# Solder_v2.net
KiCad netlist of a schematic drawn in EasyEDA
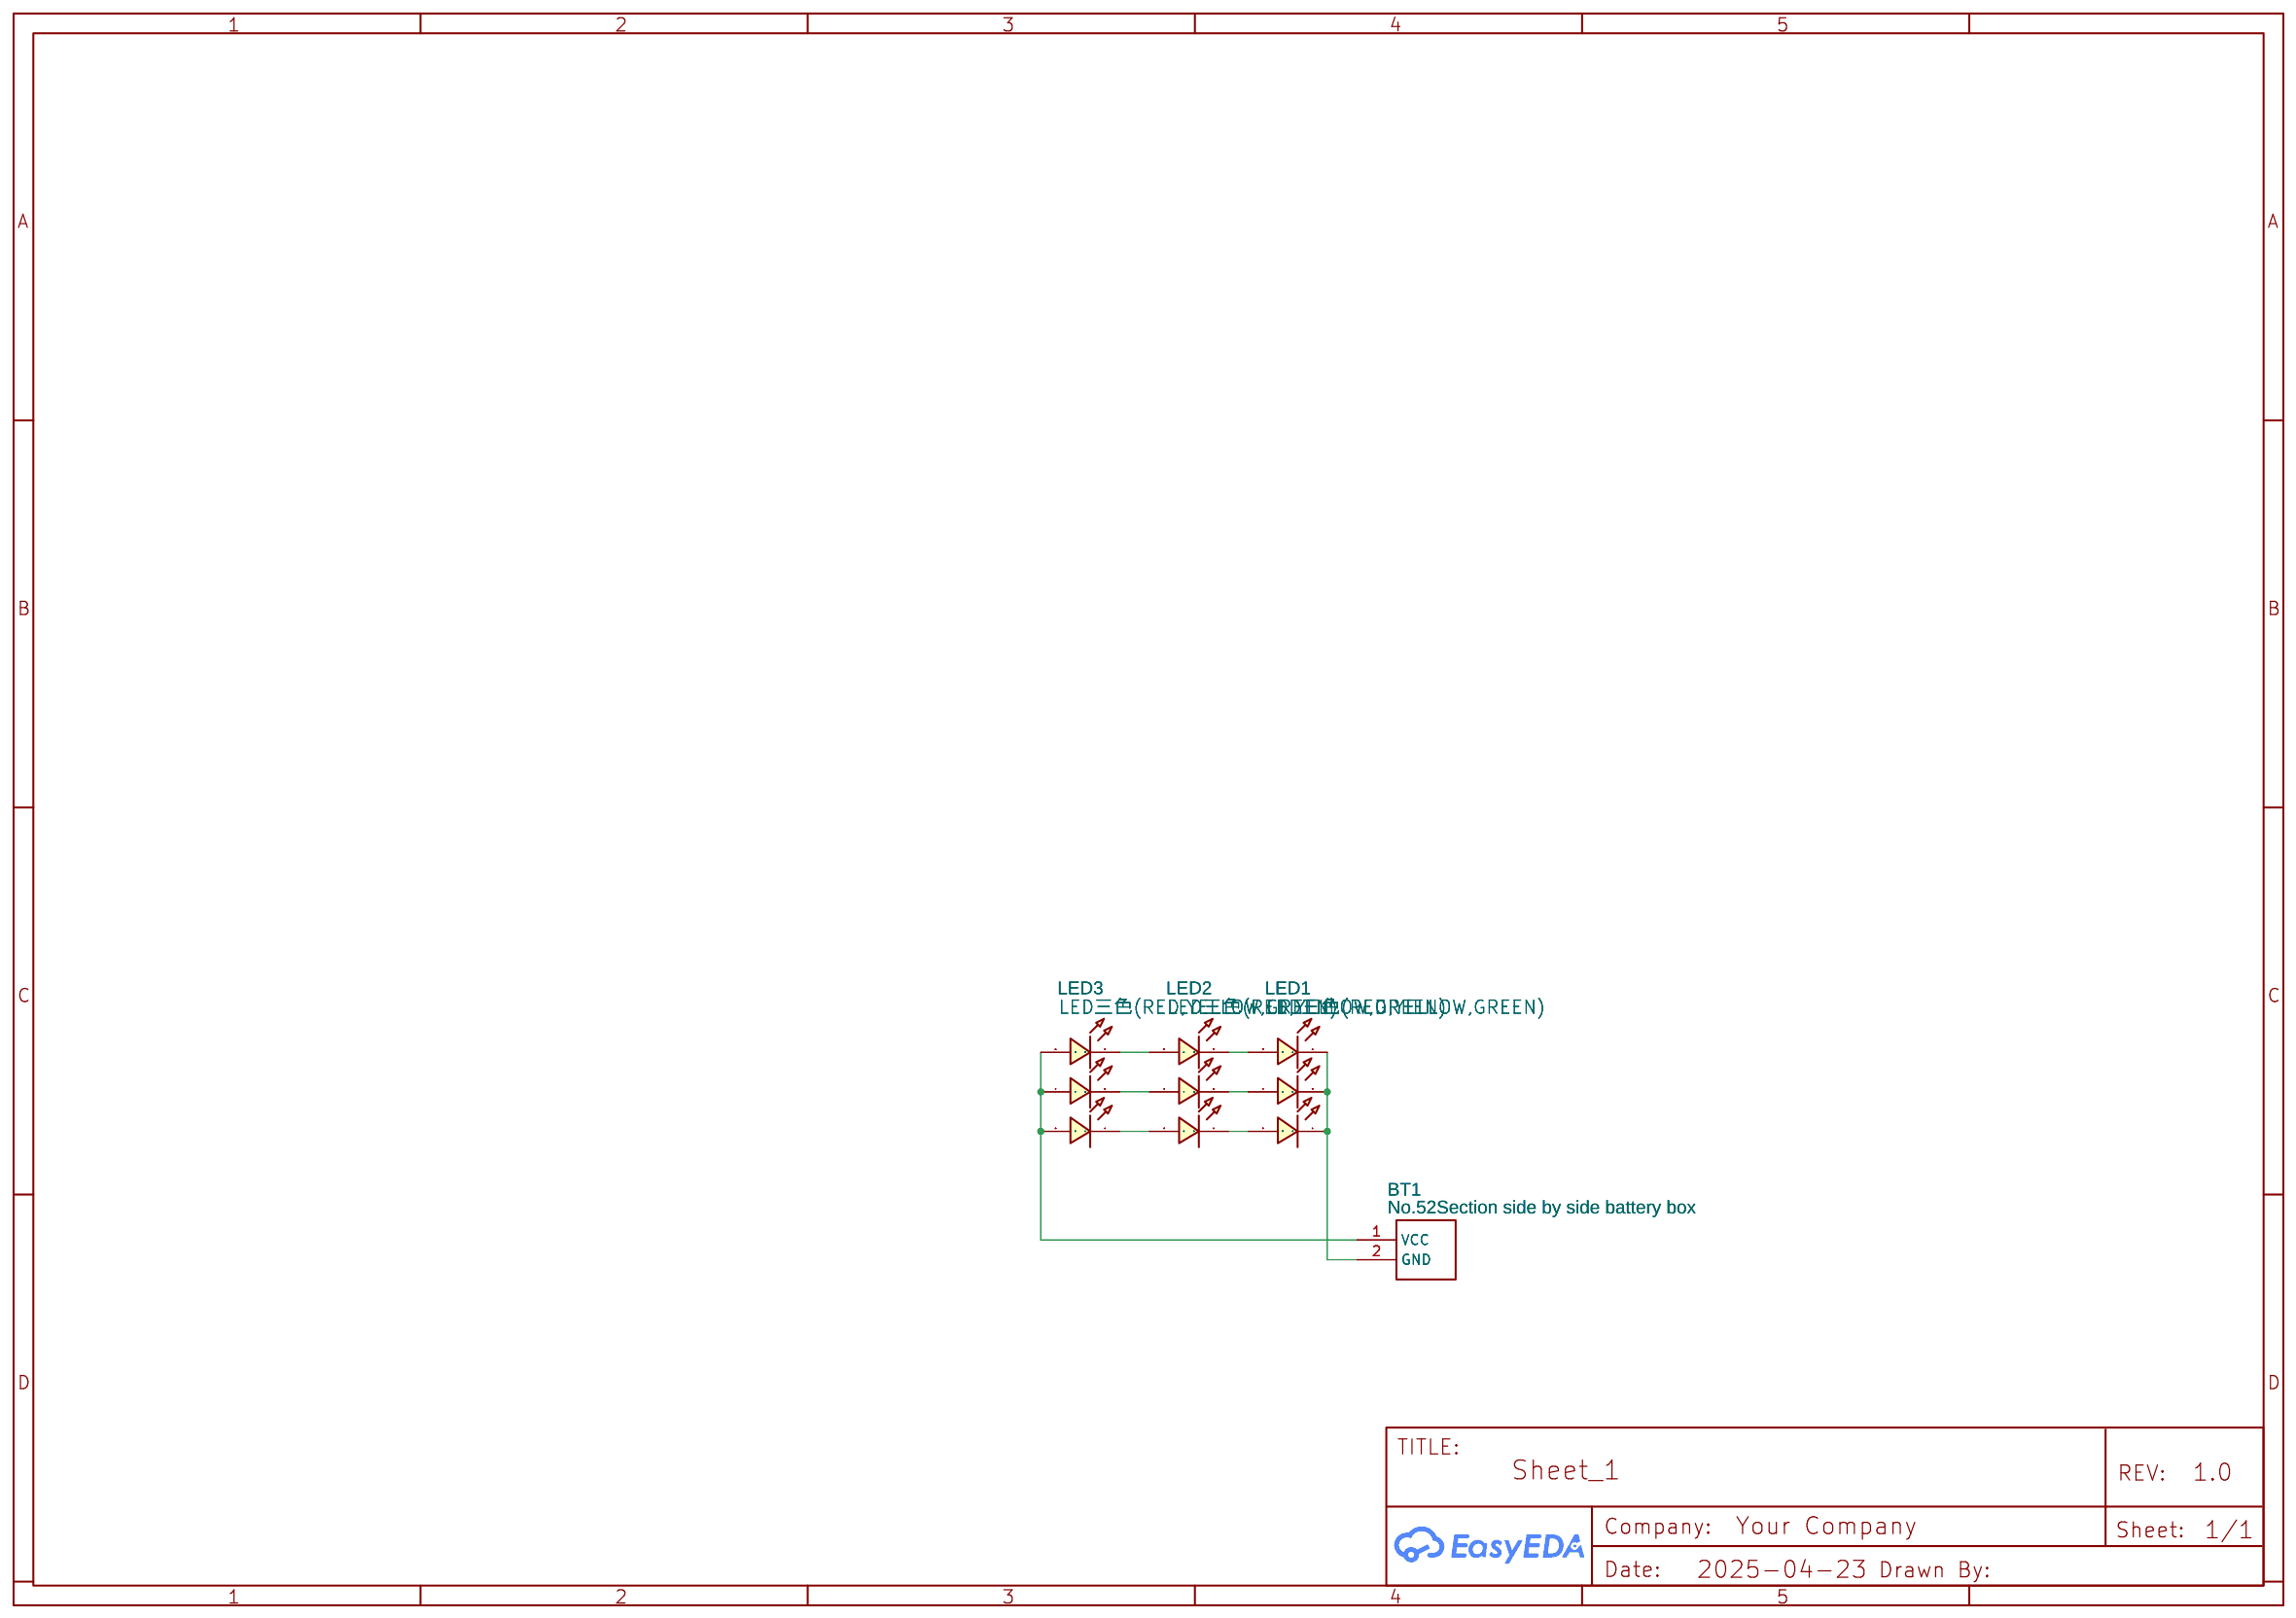
[diagram p0: schematic sheet]

(export (version "E")
  (design (tool "Eeschema 10.0.6"))
  (components
    (comp (ref "BT1")
      (value "No.52Section side by side battery box")
      (fields (field (name "Manufacturer Part") "五号2节并列电池盒") (field (name "Manufacturer") "国产"))
      (libsource (lib "") (part "No.52Section side by side battery box"))
    )
    (comp (ref "LED1")
      (value "LED三色(RED,YELLOW,GREEN)")
      (fields (field (name "Manufacturer Part") "LED三色(Red,Yellow,Green)"))
      (libsource (lib "") (part "LED三色(RED,YELLOW,GREEN)"))
    )
    (comp (ref "LED2")
      (value "LED三色(RED,YELLOW,GREEN)")
      (fields (field (name "Manufacturer Part") "LED三色(Red,Yellow,Green)"))
      (libsource (lib "") (part "LED三色(RED,YELLOW,GREEN)"))
    )
    (comp (ref "LED3")
      (value "LED三色(RED,YELLOW,GREEN)")
      (fields (field (name "Manufacturer Part") "LED三色(Red,Yellow,Green)"))
      (libsource (lib "") (part "LED三色(RED,YELLOW,GREEN)"))
    )
  )
  (nets
    (net (code "1") (name "Net-(BT1-GND)") (class "Default")
      (node (ref "BT1") (pin "2") (pinfunction "GND_2") (pintype "unspecified"))
      (node (ref "LED1") (pin "1") (pinfunction "1_1") (pintype "unspecified"))
      (node (ref "LED1") (pin "3") (pinfunction "3_3") (pintype "unspecified"))
      (node (ref "LED1") (pin "5") (pinfunction "5_5") (pintype "unspecified"))
    )
    (net (code "2") (name "Net-(BT1-VCC)") (class "Default")
      (node (ref "BT1") (pin "1") (pinfunction "VCC_1") (pintype "unspecified"))
      (node (ref "LED3") (pin "2") (pinfunction "2_2") (pintype "unspecified"))
      (node (ref "LED3") (pin "4") (pinfunction "4_4") (pintype "unspecified"))
      (node (ref "LED3") (pin "6") (pinfunction "6_6") (pintype "unspecified"))
    )
    (net (code "3") (name "Net-(LED1-Pad2)") (class "Default")
      (node (ref "LED1") (pin "2") (pinfunction "2_2") (pintype "unspecified"))
      (node (ref "LED2") (pin "1") (pinfunction "1_1") (pintype "unspecified"))
    )
    (net (code "4") (name "Net-(LED1-Pad4)") (class "Default")
      (node (ref "LED1") (pin "4") (pinfunction "4_4") (pintype "unspecified"))
      (node (ref "LED2") (pin "3") (pinfunction "3_3") (pintype "unspecified"))
    )
    (net (code "5") (name "Net-(LED1-Pad6)") (class "Default")
      (node (ref "LED1") (pin "6") (pinfunction "6_6") (pintype "unspecified"))
      (node (ref "LED2") (pin "5") (pinfunction "5_5") (pintype "unspecified"))
    )
    (net (code "6") (name "Net-(LED2-Pad2)") (class "Default")
      (node (ref "LED2") (pin "2") (pinfunction "2_2") (pintype "unspecified"))
      (node (ref "LED3") (pin "1") (pinfunction "1_1") (pintype "unspecified"))
    )
    (net (code "7") (name "Net-(LED2-Pad4)") (class "Default")
      (node (ref "LED2") (pin "4") (pinfunction "4_4") (pintype "unspecified"))
      (node (ref "LED3") (pin "3") (pinfunction "3_3") (pintype "unspecified"))
    )
    (net (code "8") (name "Net-(LED2-Pad6)") (class "Default")
      (node (ref "LED2") (pin "6") (pinfunction "6_6") (pintype "unspecified"))
      (node (ref "LED3") (pin "5") (pinfunction "5_5") (pintype "unspecified"))
    )
  )
)
